# PowerTransmitter.net
KiCad netlist of a schematic drawn in EAGLE
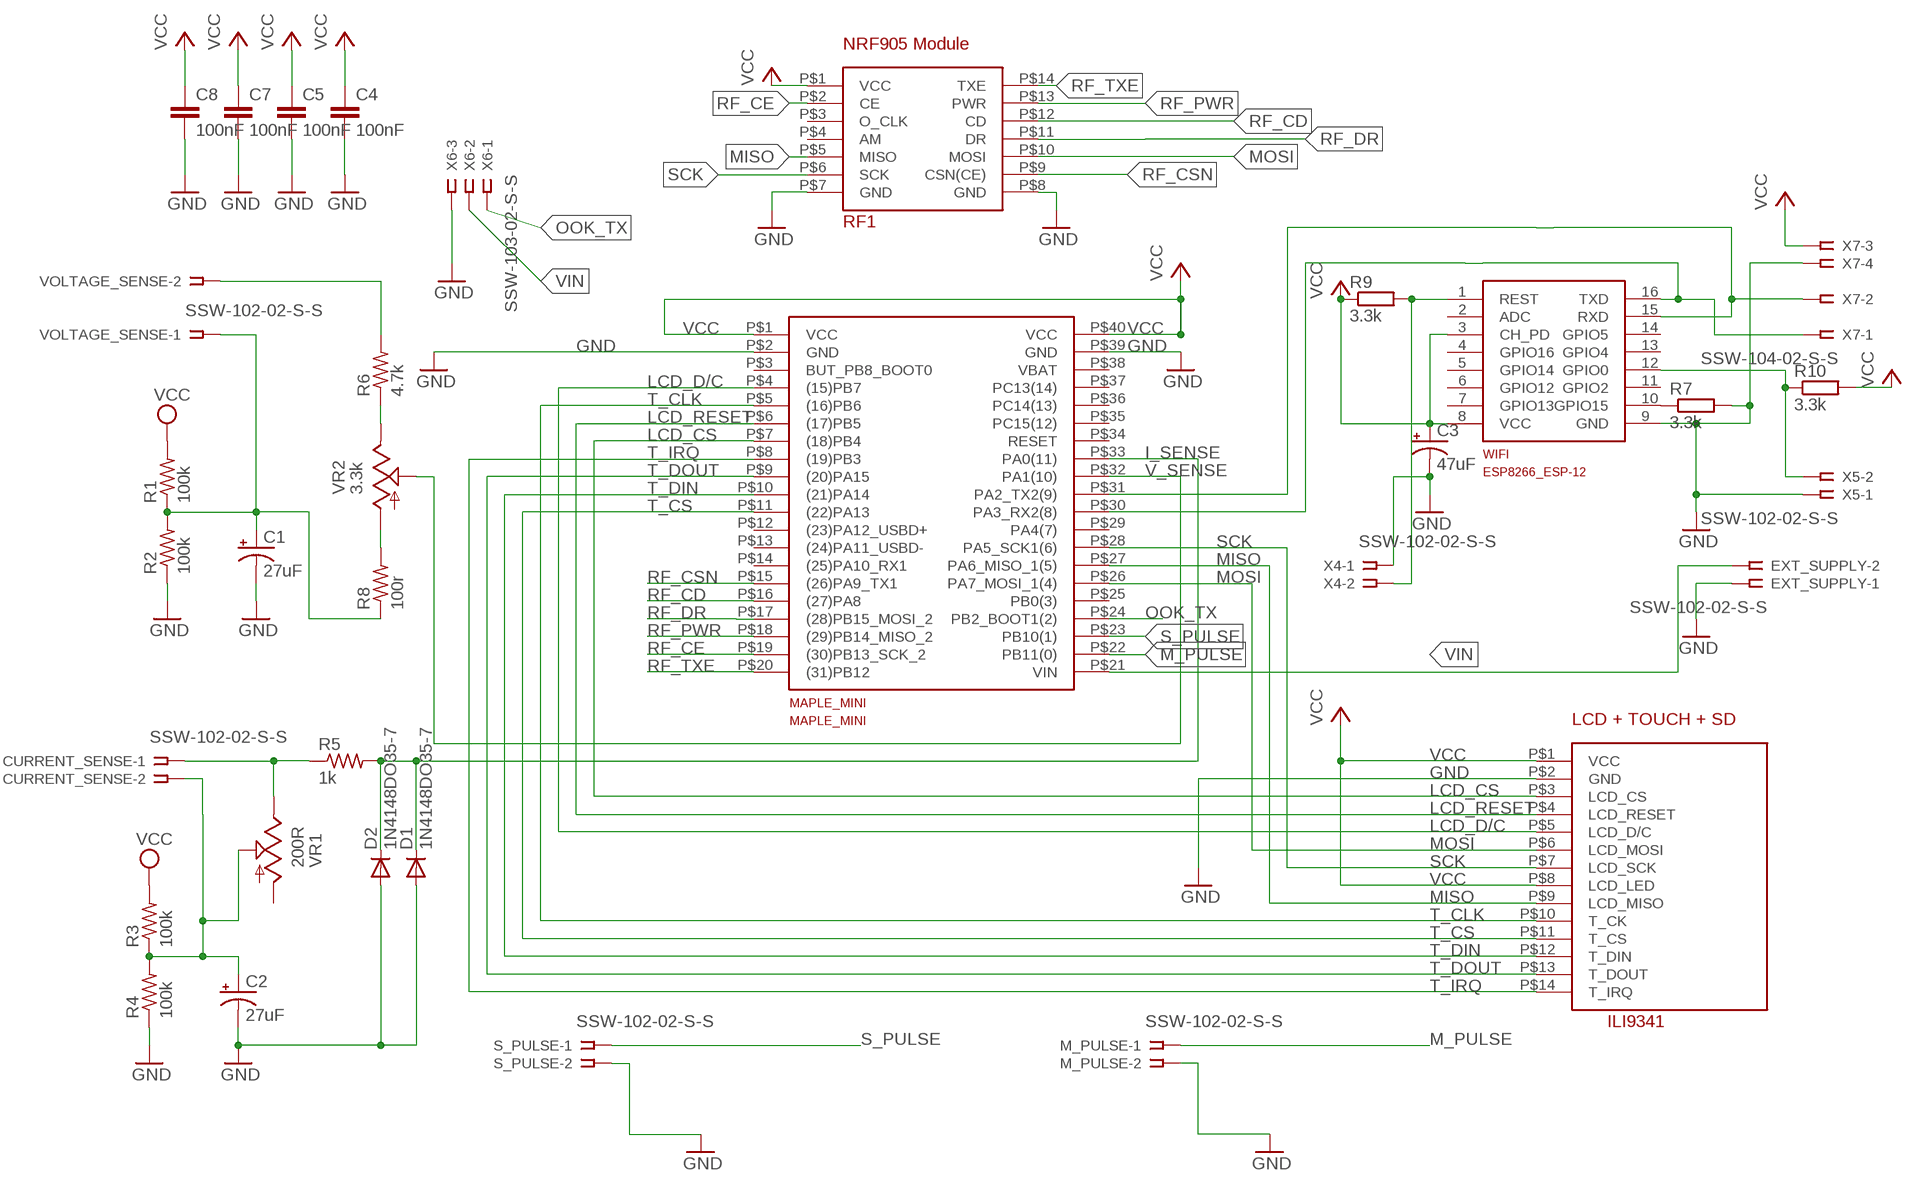
[diagram p0: schematic, sheet 1]

(export (version "E")
  (design (tool "Eeschema 10.0.6"))
  (components
    (comp (ref "C1")
      (value "27uF")
      (footprint "eagle-import:E5-8,5")
      (libsource (lib "eagle-import") (part "CPOL-USE5-8.5"))
    )
    (comp (ref "C2")
      (value "27uF")
      (footprint "eagle-import:E5-8,5")
      (libsource (lib "eagle-import") (part "CPOL-USE5-8.5"))
    )
    (comp (ref "C3")
      (value "47uF")
      (footprint "eagle-import:E5-8,5")
      (libsource (lib "eagle-import") (part "CPOL-USE5-8.5"))
    )
    (comp (ref "C4")
      (value "100nF")
      (footprint "eagle-import:C050-035X075")
      (libsource (lib "eagle-import") (part "C-EU050-035X075"))
    )
    (comp (ref "C5")
      (value "100nF")
      (footprint "eagle-import:C050-035X075")
      (libsource (lib "eagle-import") (part "C-EU050-035X075"))
    )
    (comp (ref "C7")
      (value "100nF")
      (footprint "eagle-import:C050-035X075")
      (libsource (lib "eagle-import") (part "C-EU050-035X075"))
    )
    (comp (ref "C8")
      (value "100nF")
      (footprint "eagle-import:C050-035X075")
      (libsource (lib "eagle-import") (part "C-EU050-035X075"))
    )
    (comp (ref "CURRENT_SENSE")
      (value "SSW-102-02-S-S")
      (footprint "eagle-import:SSW-102-02-S-S")
      (fields (field (name "MPN") "S1"))
      (libsource (lib "eagle-import") (part "SSW-102-02-S-S"))
    )
    (comp (ref "D1")
      (value "1N4148DO35-7")
      (footprint "eagle-import:DO35-7")
      (libsource (lib "eagle-import") (part "1N4148DO35-7"))
    )
    (comp (ref "D2")
      (value "1N4148DO35-7")
      (footprint "eagle-import:DO35-7")
      (libsource (lib "eagle-import") (part "1N4148DO35-7"))
    )
    (comp (ref "EXT_SUPPLY")
      (value "SSW-102-02-S-S")
      (footprint "eagle-import:SSW-102-02-S-S")
      (libsource (lib "eagle-import") (part "SSW-102-02-S-S"))
    )
    (comp (ref "ILI9341")
      (value "ILI9341_TOUCH_SD")
      (footprint "eagle-import:2.4_INCH")
      (libsource (lib "eagle-import") (part "ILI9341_TOUCH_SD"))
    )
    (comp (ref "MAPLE_MINI")
      (value "MAPLE_MINI")
      (footprint "eagle-import:MAPLE_MINI")
      (libsource (lib "eagle-import") (part "MAPLE_MINI"))
    )
    (comp (ref "M_PULSE")
      (value "SSW-102-02-S-S")
      (footprint "eagle-import:SSW-102-02-S-S")
      (fields (field (name "MPN") "S1"))
      (libsource (lib "eagle-import") (part "SSW-102-02-S-S"))
    )
    (comp (ref "R1")
      (value "100k")
      (footprint "eagle-import:0207_10")
      (libsource (lib "eagle-import") (part "R-US_0207/10"))
    )
    (comp (ref "R2")
      (value "100k")
      (footprint "eagle-import:0207_10")
      (libsource (lib "eagle-import") (part "R-US_0207/10"))
    )
    (comp (ref "R3")
      (value "100k")
      (footprint "eagle-import:0207_10")
      (libsource (lib "eagle-import") (part "R-US_0207/10"))
    )
    (comp (ref "R4")
      (value "100k")
      (footprint "eagle-import:0207_10")
      (libsource (lib "eagle-import") (part "R-US_0207/10"))
    )
    (comp (ref "R5")
      (value "1k")
      (footprint "eagle-import:0207_10")
      (libsource (lib "eagle-import") (part "R-US_0207/10"))
    )
    (comp (ref "R6")
      (value "4.7k")
      (footprint "eagle-import:0207_10")
      (libsource (lib "eagle-import") (part "R-US_0207/10"))
    )
    (comp (ref "R7")
      (value "3.3k")
      (footprint "eagle-import:0207_2V")
      (libsource (lib "eagle-import") (part "R-EU_0207/2V"))
    )
    (comp (ref "R8")
      (value "100r")
      (footprint "eagle-import:0207_10")
      (libsource (lib "eagle-import") (part "R-US_0207/10"))
    )
    (comp (ref "R9")
      (value "3.3k")
      (footprint "eagle-import:0207_2V")
      (libsource (lib "eagle-import") (part "R-EU_0207/2V"))
    )
    (comp (ref "R10")
      (value "3.3k")
      (footprint "eagle-import:0207_2V")
      (libsource (lib "eagle-import") (part "R-EU_0207/2V"))
    )
    (comp (ref "RF1")
      (value "NRF905_MODULE")
      (footprint "eagle-import:PIN14")
      (libsource (lib "eagle-import") (part "NRF905_MODULE"))
    )
    (comp (ref "S_PULSE")
      (value "SSW-102-02-S-S")
      (footprint "eagle-import:SSW-102-02-S-S")
      (fields (field (name "MPN") "S1"))
      (libsource (lib "eagle-import") (part "SSW-102-02-S-S"))
    )
    (comp (ref "VOLTAGE_SENSE")
      (value "SSW-102-02-S-S")
      (footprint "eagle-import:SSW-102-02-S-S")
      (libsource (lib "eagle-import") (part "SSW-102-02-S-S"))
    )
    (comp (ref "VR1")
      (value "200R")
      (footprint "eagle-import:CA9V")
      (libsource (lib "eagle-import") (part "TRIM_US-CA9V"))
    )
    (comp (ref "VR2")
      (value "3.3k")
      (footprint "eagle-import:CA9V")
      (libsource (lib "eagle-import") (part "TRIM_US-CA9V"))
    )
    (comp (ref "WIFI")
      (value "ESP8266-12")
      (footprint "eagle-import:ESP8266-ESP12")
      (libsource (lib "eagle-import") (part "ESP8266-12GPIO04/05_CORRECTED"))
    )
    (comp (ref "X4")
      (value "SSW-102-02-S-S")
      (footprint "eagle-import:SSW-102-02-S-S")
      (libsource (lib "eagle-import") (part "SSW-102-02-S-S"))
    )
    (comp (ref "X5")
      (value "SSW-102-02-S-S")
      (footprint "eagle-import:SSW-102-02-S-S")
      (libsource (lib "eagle-import") (part "SSW-102-02-S-S"))
    )
    (comp (ref "X6")
      (value "SSW-103-02-S-S")
      (footprint "eagle-import:SSW-103-02-S-S")
      (libsource (lib "eagle-import") (part "SSW-103-02-S-S"))
    )
    (comp (ref "X7")
      (value "SSW-104-02-S-S")
      (footprint "eagle-import:SSW-104-02-S-S")
      (libsource (lib "eagle-import") (part "SSW-104-02-S-S"))
    )
  )
  (nets
    (net (code "1") (name "/I_SENSE") (class "Default")
      (node (ref "D1") (pin "C") (pinfunction "C_C") (pintype "passive"))
      (node (ref "D2") (pin "C") (pinfunction "C_C") (pintype "passive"))
      (node (ref "MAPLE_MINI") (pin "P$33") (pinfunction "PA0(11)_P$33") (pintype "bidirectional"))
      (node (ref "R5") (pin "2") (pinfunction "2_2") (pintype "passive"))
    )
    (net (code "2") (name "/LCD_CS") (class "Default")
      (node (ref "ILI9341") (pin "P$3") (pinfunction "LCD_CS_P$3") (pintype "input"))
      (node (ref "MAPLE_MINI") (pin "P$7") (pinfunction "(18)PB4_P$7") (pintype "bidirectional"))
    )
    (net (code "3") (name "/LCD_D{slash}C") (class "Default")
      (node (ref "ILI9341") (pin "P$5") (pinfunction "LCD_D/C_P$5") (pintype "input"))
      (node (ref "MAPLE_MINI") (pin "P$4") (pinfunction "(15)PB7_P$4") (pintype "bidirectional"))
    )
    (net (code "4") (name "/LCD_RESET") (class "Default")
      (node (ref "ILI9341") (pin "P$4") (pinfunction "LCD_RESET_P$4") (pintype "input"))
      (node (ref "MAPLE_MINI") (pin "P$6") (pinfunction "(17)PB5_P$6") (pintype "bidirectional"))
    )
    (net (code "5") (name "/T_CLK") (class "Default")
      (node (ref "ILI9341") (pin "P$10") (pinfunction "T_CK_P$10") (pintype "input"))
      (node (ref "MAPLE_MINI") (pin "P$5") (pinfunction "(16)PB6_P$5") (pintype "bidirectional"))
    )
    (net (code "6") (name "/T_CS") (class "Default")
      (node (ref "ILI9341") (pin "P$11") (pinfunction "T_CS_P$11") (pintype "bidirectional"))
      (node (ref "MAPLE_MINI") (pin "P$11") (pinfunction "(22)PA13_P$11") (pintype "bidirectional"))
    )
    (net (code "7") (name "/T_DIN") (class "Default")
      (node (ref "ILI9341") (pin "P$12") (pinfunction "T_DIN_P$12") (pintype "input"))
      (node (ref "MAPLE_MINI") (pin "P$10") (pinfunction "(21)PA14_P$10") (pintype "bidirectional"))
    )
    (net (code "8") (name "/T_DOUT") (class "Default")
      (node (ref "ILI9341") (pin "P$13") (pinfunction "T_DOUT_P$13") (pintype "output"))
      (node (ref "MAPLE_MINI") (pin "P$9") (pinfunction "(20)PA15_P$9") (pintype "bidirectional"))
    )
    (net (code "9") (name "/T_IRQ") (class "Default")
      (node (ref "ILI9341") (pin "P$14") (pinfunction "T_IRQ_P$14") (pintype "output"))
      (node (ref "MAPLE_MINI") (pin "P$8") (pinfunction "(19)PB3_P$8") (pintype "bidirectional"))
    )
    (net (code "10") (name "/V_SENSE") (class "Default")
      (node (ref "MAPLE_MINI") (pin "P$32") (pinfunction "PA1(10)_P$32") (pintype "bidirectional"))
      (node (ref "VR2") (pin "S") (pinfunction "S_S") (pintype "passive"))
    )
    (net (code "11") (name "GND") (class "Default")
      (node (ref "C1") (pin "-") (pinfunction "-_-") (pintype "passive"))
      (node (ref "C2") (pin "-") (pinfunction "-_-") (pintype "passive"))
      (node (ref "C3") (pin "-") (pinfunction "-_-") (pintype "passive"))
      (node (ref "C4") (pin "2") (pinfunction "2_2") (pintype "passive"))
      (node (ref "C5") (pin "2") (pinfunction "2_2") (pintype "passive"))
      (node (ref "C7") (pin "2") (pinfunction "2_2") (pintype "passive"))
      (node (ref "C8") (pin "2") (pinfunction "2_2") (pintype "passive"))
      (node (ref "D1") (pin "A") (pinfunction "A_A") (pintype "passive"))
      (node (ref "D2") (pin "A") (pinfunction "A_A") (pintype "passive"))
      (node (ref "EXT_SUPPLY") (pin "1") (pinfunction "1_1") (pintype "passive"))
      (node (ref "ILI9341") (pin "P$2") (pinfunction "GND_P$2") (pintype "power_in"))
      (node (ref "MAPLE_MINI") (pin "P$2") (pinfunction "GND_P$2") (pintype "power_in"))
      (node (ref "MAPLE_MINI") (pin "P$39") (pinfunction "GND_P$39") (pintype "power_in"))
      (node (ref "M_PULSE") (pin "2") (pinfunction "1_2") (pintype "passive"))
      (node (ref "R2") (pin "1") (pinfunction "1_1") (pintype "passive"))
      (node (ref "R4") (pin "1") (pinfunction "1_1") (pintype "passive"))
      (node (ref "R7") (pin "2") (pinfunction "2_2") (pintype "passive"))
      (node (ref "RF1") (pin "P$7") (pinfunction "GND_P$7") (pintype "power_in"))
      (node (ref "RF1") (pin "P$8") (pinfunction "GND_P$8") (pintype "power_in"))
      (node (ref "S_PULSE") (pin "2") (pinfunction "1_2") (pintype "passive"))
      (node (ref "WIFI") (pin "9") (pinfunction "GND_9") (pintype "bidirectional"))
      (node (ref "X4") (pin "1") (pinfunction "1_1") (pintype "passive"))
      (node (ref "X5") (pin "1") (pinfunction "1_1") (pintype "passive"))
      (node (ref "X6") (pin "3") (pinfunction "1_3") (pintype "passive"))
      (node (ref "X7") (pin "4") (pinfunction "1_4") (pintype "passive"))
    )
    (net (code "12") (name "MISO") (class "Default")
      (node (ref "ILI9341") (pin "P$9") (pinfunction "LCD_MISO_P$9") (pintype "bidirectional"))
      (node (ref "MAPLE_MINI") (pin "P$27") (pinfunction "PA6_MISO_1(5)_P$27") (pintype "bidirectional"))
      (node (ref "RF1") (pin "P$5") (pinfunction "MISO_P$5") (pintype "output"))
    )
    (net (code "13") (name "MOSI") (class "Default")
      (node (ref "ILI9341") (pin "P$6") (pinfunction "LCD_MOSI_P$6") (pintype "input"))
      (node (ref "MAPLE_MINI") (pin "P$26") (pinfunction "PA7_MOSI_1(4)_P$26") (pintype "bidirectional"))
      (node (ref "RF1") (pin "P$10") (pinfunction "MOSI_P$10") (pintype "input"))
    )
    (net (code "14") (name "M_PULSE") (class "Default")
      (node (ref "MAPLE_MINI") (pin "P$22") (pinfunction "PB11(0)_P$22") (pintype "bidirectional"))
      (node (ref "M_PULSE") (pin "1") (pinfunction "1_1") (pintype "passive"))
    )
    (net (code "15") (name "Net-(C1-Pad+)") (class "Default")
      (node (ref "C1") (pin "+") (pinfunction "+_+") (pintype "passive"))
      (node (ref "R1") (pin "1") (pinfunction "1_1") (pintype "passive"))
      (node (ref "R2") (pin "2") (pinfunction "2_2") (pintype "passive"))
      (node (ref "R8") (pin "1") (pinfunction "1_1") (pintype "passive"))
      (node (ref "VOLTAGE_SENSE") (pin "1") (pinfunction "1_1") (pintype "passive"))
    )
    (net (code "16") (name "Net-(CURRENT_SENSE-Pad1)") (class "Default")
      (node (ref "CURRENT_SENSE") (pin "1") (pinfunction "1_1") (pintype "passive"))
      (node (ref "R5") (pin "1") (pinfunction "1_1") (pintype "passive"))
      (node (ref "VR1") (pin "E") (pinfunction "E_E") (pintype "passive"))
    )
    (net (code "17") (name "Net-(CURRENT_SENSEB-1)") (class "Default")
      (node (ref "C2") (pin "+") (pinfunction "+_+") (pintype "passive"))
      (node (ref "CURRENT_SENSE") (pin "2") (pinfunction "1_2") (pintype "passive"))
      (node (ref "R3") (pin "1") (pinfunction "1_1") (pintype "passive"))
      (node (ref "R4") (pin "2") (pinfunction "2_2") (pintype "passive"))
      (node (ref "VR1") (pin "S") (pinfunction "S_S") (pintype "passive"))
    )
    (net (code "18") (name "Net-(MAPLE_MINI-PA2_TX2(9))") (class "Default")
      (node (ref "MAPLE_MINI") (pin "P$31") (pinfunction "PA2_TX2(9)_P$31") (pintype "bidirectional"))
      (node (ref "WIFI") (pin "15") (pinfunction "RXD_15") (pintype "bidirectional"))
      (node (ref "X7") (pin "2") (pinfunction "1_2") (pintype "passive"))
    )
    (net (code "19") (name "Net-(MAPLE_MINI-PA3_RX2(8))") (class "Default")
      (node (ref "MAPLE_MINI") (pin "P$30") (pinfunction "PA3_RX2(8)_P$30") (pintype "bidirectional"))
      (node (ref "WIFI") (pin "16") (pinfunction "TXD_16") (pintype "bidirectional"))
      (node (ref "X7") (pin "1") (pinfunction "1_1") (pintype "passive"))
    )
    (net (code "20") (name "Net-(R6-Pad1)") (class "Default")
      (node (ref "R6") (pin "1") (pinfunction "1_1") (pintype "passive"))
      (node (ref "VR2") (pin "E") (pinfunction "E_E") (pintype "passive"))
    )
    (net (code "21") (name "Net-(R8-Pad2)") (class "Default")
      (node (ref "R8") (pin "2") (pinfunction "2_2") (pintype "passive"))
      (node (ref "VR2") (pin "A") (pinfunction "A_A") (pintype "passive"))
    )
    (net (code "22") (name "Net-(VOLTAGE_SENSEB-1)") (class "Default")
      (node (ref "R6") (pin "2") (pinfunction "2_2") (pintype "passive"))
      (node (ref "VOLTAGE_SENSE") (pin "2") (pinfunction "1_2") (pintype "passive"))
    )
    (net (code "23") (name "Net-(WIFI-GPIO0)") (class "Default")
      (node (ref "R10") (pin "1") (pinfunction "1_1") (pintype "passive"))
      (node (ref "WIFI") (pin "12") (pinfunction "GPIO0_12") (pintype "bidirectional"))
      (node (ref "X5") (pin "2") (pinfunction "1_2") (pintype "passive"))
    )
    (net (code "24") (name "Net-(WIFI-GPIO15)") (class "Default")
      (node (ref "R7") (pin "1") (pinfunction "1_1") (pintype "passive"))
      (node (ref "WIFI") (pin "10") (pinfunction "GPIO15_10") (pintype "bidirectional"))
    )
    (net (code "25") (name "Net-(WIFI-REST)") (class "Default")
      (node (ref "R9") (pin "2") (pinfunction "2_2") (pintype "passive"))
      (node (ref "WIFI") (pin "1") (pinfunction "REST_1") (pintype "bidirectional"))
      (node (ref "X4") (pin "2") (pinfunction "1_2") (pintype "passive"))
    )
    (net (code "26") (name "OOK_TX") (class "Default")
      (node (ref "MAPLE_MINI") (pin "P$24") (pinfunction "PB2_BOOT1(2)_P$24") (pintype "bidirectional"))
      (node (ref "X6") (pin "1") (pinfunction "1_1") (pintype "passive"))
    )
    (net (code "27") (name "RF_CD") (class "Default")
      (node (ref "MAPLE_MINI") (pin "P$16") (pinfunction "(27)PA8_P$16") (pintype "bidirectional"))
      (node (ref "RF1") (pin "P$12") (pinfunction "CD_P$12") (pintype "bidirectional"))
    )
    (net (code "28") (name "RF_CE") (class "Default")
      (node (ref "MAPLE_MINI") (pin "P$19") (pinfunction "(30)PB13_SCK_2_P$19") (pintype "bidirectional"))
      (node (ref "RF1") (pin "P$2") (pinfunction "CE_P$2") (pintype "input"))
    )
    (net (code "29") (name "RF_CSN") (class "Default")
      (node (ref "MAPLE_MINI") (pin "P$15") (pinfunction "(26)PA9_TX1_P$15") (pintype "bidirectional"))
      (node (ref "RF1") (pin "P$9") (pinfunction "CSN(CE)_P$9") (pintype "input"))
    )
    (net (code "30") (name "RF_DR") (class "Default")
      (node (ref "MAPLE_MINI") (pin "P$17") (pinfunction "(28)PB15_MOSI_2_P$17") (pintype "bidirectional"))
      (node (ref "RF1") (pin "P$11") (pinfunction "DR_P$11") (pintype "bidirectional"))
    )
    (net (code "31") (name "RF_PWR") (class "Default")
      (node (ref "MAPLE_MINI") (pin "P$18") (pinfunction "(29)PB14_MISO_2_P$18") (pintype "bidirectional"))
      (node (ref "RF1") (pin "P$13") (pinfunction "PWR_P$13") (pintype "bidirectional"))
    )
    (net (code "32") (name "RF_TXE") (class "Default")
      (node (ref "MAPLE_MINI") (pin "P$20") (pinfunction "(31)PB12_P$20") (pintype "bidirectional"))
      (node (ref "RF1") (pin "P$14") (pinfunction "TXE_P$14") (pintype "bidirectional"))
    )
    (net (code "33") (name "SCK") (class "Default")
      (node (ref "ILI9341") (pin "P$7") (pinfunction "LCD_SCK_P$7") (pintype "input"))
      (node (ref "MAPLE_MINI") (pin "P$28") (pinfunction "PA5_SCK1(6)_P$28") (pintype "bidirectional"))
      (node (ref "RF1") (pin "P$6") (pinfunction "SCK_P$6") (pintype "bidirectional"))
    )
    (net (code "34") (name "S_PULSE") (class "Default")
      (node (ref "MAPLE_MINI") (pin "P$23") (pinfunction "PB10(1)_P$23") (pintype "bidirectional"))
      (node (ref "S_PULSE") (pin "1") (pinfunction "1_1") (pintype "passive"))
    )
    (net (code "35") (name "VCC") (class "Default")
      (node (ref "C3") (pin "+") (pinfunction "+_+") (pintype "passive"))
      (node (ref "C4") (pin "1") (pinfunction "1_1") (pintype "passive"))
      (node (ref "C5") (pin "1") (pinfunction "1_1") (pintype "passive"))
      (node (ref "C7") (pin "1") (pinfunction "1_1") (pintype "passive"))
      (node (ref "C8") (pin "1") (pinfunction "1_1") (pintype "passive"))
      (node (ref "ILI9341") (pin "P$1") (pinfunction "VCC_P$1") (pintype "power_in"))
      (node (ref "ILI9341") (pin "P$8") (pinfunction "LCD_LED_P$8") (pintype "bidirectional"))
      (node (ref "MAPLE_MINI") (pin "P$1") (pinfunction "VCC_P$1") (pintype "bidirectional"))
      (node (ref "MAPLE_MINI") (pin "P$40") (pinfunction "VCC_P$40") (pintype "bidirectional"))
      (node (ref "R1") (pin "2") (pinfunction "2_2") (pintype "passive"))
      (node (ref "R10") (pin "2") (pinfunction "2_2") (pintype "passive"))
      (node (ref "R3") (pin "2") (pinfunction "2_2") (pintype "passive"))
      (node (ref "R9") (pin "1") (pinfunction "1_1") (pintype "passive"))
      (node (ref "RF1") (pin "P$1") (pinfunction "VCC_P$1") (pintype "power_in"))
      (node (ref "WIFI") (pin "3") (pinfunction "CH_PD_3") (pintype "bidirectional"))
      (node (ref "WIFI") (pin "8") (pinfunction "VCC_8") (pintype "bidirectional"))
      (node (ref "X7") (pin "3") (pinfunction "1_3") (pintype "passive"))
    )
    (net (code "36") (name "VIN") (class "Default")
      (node (ref "EXT_SUPPLY") (pin "2") (pinfunction "1_2") (pintype "passive"))
      (node (ref "MAPLE_MINI") (pin "P$21") (pinfunction "VIN_P$21") (pintype "power_in"))
      (node (ref "X6") (pin "2") (pinfunction "1_2") (pintype "passive"))
    )
    (net (code "37") (name "unconnected-(MAPLE_MINI-(23)PA12_USBD+-PadP$12)") (class "Default")
      (node (ref "MAPLE_MINI") (pin "P$12") (pinfunction "(23)PA12_USBD+_P$12") (pintype "bidirectional"))
    )
    (net (code "38") (name "unconnected-(MAPLE_MINI-(24)PA11_USBD--PadP$13)") (class "Default")
      (node (ref "MAPLE_MINI") (pin "P$13") (pinfunction "(24)PA11_USBD-_P$13") (pintype "bidirectional"))
    )
    (net (code "39") (name "unconnected-(MAPLE_MINI-(25)PA10_RX1-PadP$14)") (class "Default")
      (node (ref "MAPLE_MINI") (pin "P$14") (pinfunction "(25)PA10_RX1_P$14") (pintype "bidirectional"))
    )
    (net (code "40") (name "unconnected-(MAPLE_MINI-BUT_PB8_BOOT0-PadP$3)") (class "Default")
      (node (ref "MAPLE_MINI") (pin "P$3") (pinfunction "BUT_PB8_BOOT0_P$3") (pintype "bidirectional"))
    )
    (net (code "41") (name "unconnected-(MAPLE_MINI-PA4(7)-PadP$29)") (class "Default")
      (node (ref "MAPLE_MINI") (pin "P$29") (pinfunction "PA4(7)_P$29") (pintype "bidirectional"))
    )
    (net (code "42") (name "unconnected-(MAPLE_MINI-PB0(3)-PadP$25)") (class "Default")
      (node (ref "MAPLE_MINI") (pin "P$25") (pinfunction "PB0(3)_P$25") (pintype "bidirectional"))
    )
    (net (code "43") (name "unconnected-(MAPLE_MINI-PC13(14)-PadP$37)") (class "Default")
      (node (ref "MAPLE_MINI") (pin "P$37") (pinfunction "PC13(14)_P$37") (pintype "bidirectional"))
    )
    (net (code "44") (name "unconnected-(MAPLE_MINI-PC14(13)-PadP$36)") (class "Default")
      (node (ref "MAPLE_MINI") (pin "P$36") (pinfunction "PC14(13)_P$36") (pintype "bidirectional"))
    )
    (net (code "45") (name "unconnected-(MAPLE_MINI-PC15(12)-PadP$35)") (class "Default")
      (node (ref "MAPLE_MINI") (pin "P$35") (pinfunction "PC15(12)_P$35") (pintype "bidirectional"))
    )
    (net (code "46") (name "unconnected-(MAPLE_MINI-RESET-PadP$34)") (class "Default")
      (node (ref "MAPLE_MINI") (pin "P$34") (pinfunction "RESET_P$34") (pintype "bidirectional"))
    )
    (net (code "47") (name "unconnected-(MAPLE_MINI-VBAT-PadP$38)") (class "Default")
      (node (ref "MAPLE_MINI") (pin "P$38") (pinfunction "VBAT_P$38") (pintype "bidirectional"))
    )
    (net (code "48") (name "unconnected-(RF1-AM-PadP$4)") (class "Default")
      (node (ref "RF1") (pin "P$4") (pinfunction "AM_P$4") (pintype "output"))
    )
    (net (code "49") (name "unconnected-(RF1-O_CLK-PadP$3)") (class "Default")
      (node (ref "RF1") (pin "P$3") (pinfunction "O_CLK_P$3") (pintype "output"))
    )
    (net (code "50") (name "unconnected-(VR1-PadA)") (class "Default")
      (node (ref "VR1") (pin "A") (pinfunction "A_A") (pintype "passive"))
    )
    (net (code "51") (name "unconnected-(WIFI-ADC-Pad2)") (class "Default")
      (node (ref "WIFI") (pin "2") (pinfunction "ADC_2") (pintype "bidirectional"))
    )
    (net (code "52") (name "unconnected-(WIFI-GPIO2-Pad11)") (class "Default")
      (node (ref "WIFI") (pin "11") (pinfunction "GPIO2_11") (pintype "bidirectional"))
    )
    (net (code "53") (name "unconnected-(WIFI-GPIO4-Pad13)") (class "Default")
      (node (ref "WIFI") (pin "13") (pinfunction "GPIO4_13") (pintype "bidirectional"))
    )
    (net (code "54") (name "unconnected-(WIFI-GPIO5-Pad14)") (class "Default")
      (node (ref "WIFI") (pin "14") (pinfunction "GPIO5_14") (pintype "bidirectional"))
    )
    (net (code "55") (name "unconnected-(WIFI-GPIO12-Pad6)") (class "Default")
      (node (ref "WIFI") (pin "6") (pinfunction "GPIO12_6") (pintype "bidirectional"))
    )
    (net (code "56") (name "unconnected-(WIFI-GPIO13-Pad7)") (class "Default")
      (node (ref "WIFI") (pin "7") (pinfunction "GPIO13_7") (pintype "bidirectional"))
    )
    (net (code "57") (name "unconnected-(WIFI-GPIO14-Pad5)") (class "Default")
      (node (ref "WIFI") (pin "5") (pinfunction "GPIO14_5") (pintype "bidirectional"))
    )
    (net (code "58") (name "unconnected-(WIFI-GPIO16-Pad4)") (class "Default")
      (node (ref "WIFI") (pin "4") (pinfunction "GPIO16_4") (pintype "bidirectional"))
    )
  )
)
